# P3DA.net
KiCad netlist of a schematic drawn in EAGLE
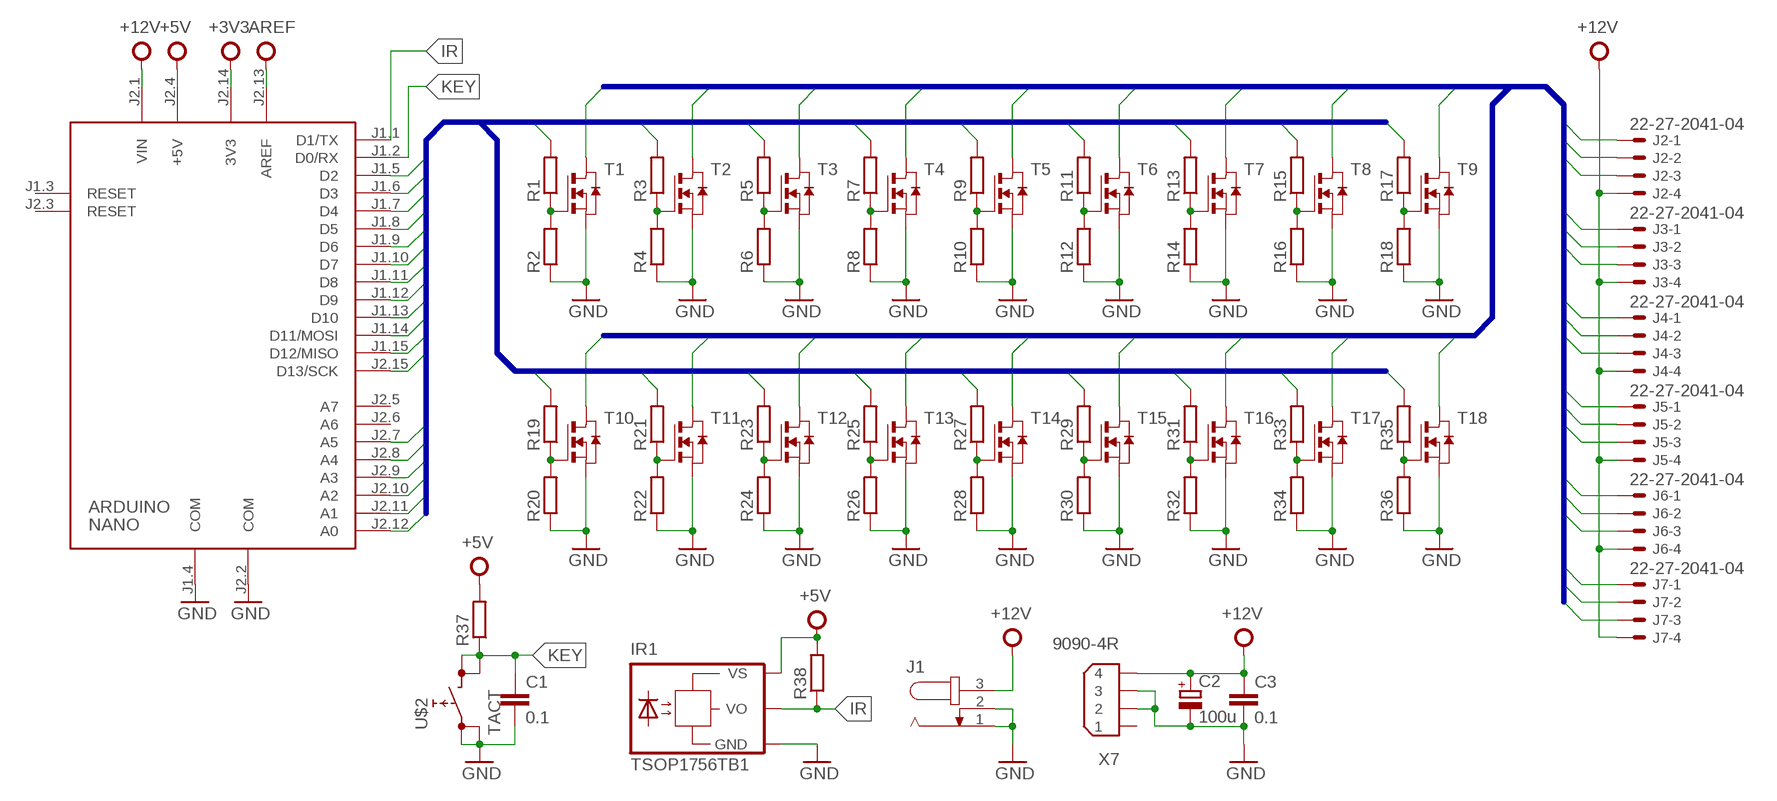
[diagram p0: schematic, sheet 1]

(export (version "E")
  (design (tool "Eeschema 10.0.6"))
  (components
    (comp (ref "ARDUINO")
      (value "NANO")
      (footprint "eagle-import:ARDUINO_NANO2")
      (libsource (lib "eagle-import") (part "ARDUINO_NANO2"))
    )
    (comp (ref "C1")
      (value "0.1")
      (footprint "eagle-import:C0805")
      (libsource (lib "eagle-import") (part "C-EUC0805"))
    )
    (comp (ref "C2")
      (value "100u")
      (footprint "eagle-import:E5-13")
      (libsource (lib "eagle-import") (part "CPOL-EUE5-13"))
    )
    (comp (ref "C3")
      (value "0.1")
      (footprint "eagle-import:C1206")
      (libsource (lib "eagle-import") (part "C-EUC1206"))
    )
    (comp (ref "IR1")
      (value "TSOP1756TB1")
      (footprint "eagle-import:TSOP17_TB1")
      (libsource (lib "eagle-import") (part "TSOP17TB156"))
    )
    (comp (ref "J1")
      (value "JACK-PLUG1")
      (footprint "eagle-import:SPC4078")
      (libsource (lib "eagle-import") (part "JACK-PLUG1"))
    )
    (comp (ref "J2")
      (value "22-27-2041-04")
      (footprint "eagle-import:6410-04")
      (libsource (lib "eagle-import") (part "22-?-0427-2041"))
    )
    (comp (ref "J3")
      (value "22-27-2041-04")
      (footprint "eagle-import:6410-04")
      (libsource (lib "eagle-import") (part "22-?-0427-2041"))
    )
    (comp (ref "J4")
      (value "22-27-2041-04")
      (footprint "eagle-import:6410-04")
      (libsource (lib "eagle-import") (part "22-?-0427-2041"))
    )
    (comp (ref "J5")
      (value "22-27-2041-04")
      (footprint "eagle-import:6410-04")
      (libsource (lib "eagle-import") (part "22-?-0427-2041"))
    )
    (comp (ref "J6")
      (value "22-27-2041-04")
      (footprint "eagle-import:6410-04")
      (libsource (lib "eagle-import") (part "22-?-0427-2041"))
    )
    (comp (ref "J7")
      (value "22-27-2041-04")
      (footprint "eagle-import:6410-04")
      (libsource (lib "eagle-import") (part "22-?-0427-2041"))
    )
    (comp (ref "R1")
      (value "R-EU_R0805")
      (footprint "eagle-import:R0805")
      (libsource (lib "eagle-import") (part "R-EU_R0805"))
    )
    (comp (ref "R2")
      (value "R-EU_R0805")
      (footprint "eagle-import:R0805")
      (libsource (lib "eagle-import") (part "R-EU_R0805"))
    )
    (comp (ref "R3")
      (value "R-EU_R0805")
      (footprint "eagle-import:R0805")
      (libsource (lib "eagle-import") (part "R-EU_R0805"))
    )
    (comp (ref "R4")
      (value "R-EU_R0805")
      (footprint "eagle-import:R0805")
      (libsource (lib "eagle-import") (part "R-EU_R0805"))
    )
    (comp (ref "R5")
      (value "R-EU_R0805")
      (footprint "eagle-import:R0805")
      (libsource (lib "eagle-import") (part "R-EU_R0805"))
    )
    (comp (ref "R6")
      (value "R-EU_R0805")
      (footprint "eagle-import:R0805")
      (libsource (lib "eagle-import") (part "R-EU_R0805"))
    )
    (comp (ref "R7")
      (value "R-EU_R0805")
      (footprint "eagle-import:R0805")
      (libsource (lib "eagle-import") (part "R-EU_R0805"))
    )
    (comp (ref "R8")
      (value "R-EU_R0805")
      (footprint "eagle-import:R0805")
      (libsource (lib "eagle-import") (part "R-EU_R0805"))
    )
    (comp (ref "R9")
      (value "R-EU_R0805")
      (footprint "eagle-import:R0805")
      (libsource (lib "eagle-import") (part "R-EU_R0805"))
    )
    (comp (ref "R10")
      (value "R-EU_R0805")
      (footprint "eagle-import:R0805")
      (libsource (lib "eagle-import") (part "R-EU_R0805"))
    )
    (comp (ref "R11")
      (value "R-EU_R0805")
      (footprint "eagle-import:R0805")
      (libsource (lib "eagle-import") (part "R-EU_R0805"))
    )
    (comp (ref "R12")
      (value "R-EU_R0805")
      (footprint "eagle-import:R0805")
      (libsource (lib "eagle-import") (part "R-EU_R0805"))
    )
    (comp (ref "R13")
      (value "R-EU_R0805")
      (footprint "eagle-import:R0805")
      (libsource (lib "eagle-import") (part "R-EU_R0805"))
    )
    (comp (ref "R14")
      (value "R-EU_R0805")
      (footprint "eagle-import:R0805")
      (libsource (lib "eagle-import") (part "R-EU_R0805"))
    )
    (comp (ref "R15")
      (value "R-EU_R0805")
      (footprint "eagle-import:R0805")
      (libsource (lib "eagle-import") (part "R-EU_R0805"))
    )
    (comp (ref "R16")
      (value "R-EU_R0805")
      (footprint "eagle-import:R0805")
      (libsource (lib "eagle-import") (part "R-EU_R0805"))
    )
    (comp (ref "R17")
      (value "R-EU_R0805")
      (footprint "eagle-import:R0805")
      (libsource (lib "eagle-import") (part "R-EU_R0805"))
    )
    (comp (ref "R18")
      (value "R-EU_R0805")
      (footprint "eagle-import:R0805")
      (libsource (lib "eagle-import") (part "R-EU_R0805"))
    )
    (comp (ref "R19")
      (value "R-EU_R0805")
      (footprint "eagle-import:R0805")
      (libsource (lib "eagle-import") (part "R-EU_R0805"))
    )
    (comp (ref "R20")
      (value "R-EU_R0805")
      (footprint "eagle-import:R0805")
      (libsource (lib "eagle-import") (part "R-EU_R0805"))
    )
    (comp (ref "R21")
      (value "R-EU_R0805")
      (footprint "eagle-import:R0805")
      (libsource (lib "eagle-import") (part "R-EU_R0805"))
    )
    (comp (ref "R22")
      (value "R-EU_R0805")
      (footprint "eagle-import:R0805")
      (libsource (lib "eagle-import") (part "R-EU_R0805"))
    )
    (comp (ref "R23")
      (value "R-EU_R0805")
      (footprint "eagle-import:R0805")
      (libsource (lib "eagle-import") (part "R-EU_R0805"))
    )
    (comp (ref "R24")
      (value "R-EU_R0805")
      (footprint "eagle-import:R0805")
      (libsource (lib "eagle-import") (part "R-EU_R0805"))
    )
    (comp (ref "R25")
      (value "R-EU_R0805")
      (footprint "eagle-import:R0805")
      (libsource (lib "eagle-import") (part "R-EU_R0805"))
    )
    (comp (ref "R26")
      (value "R-EU_R0805")
      (footprint "eagle-import:R0805")
      (libsource (lib "eagle-import") (part "R-EU_R0805"))
    )
    (comp (ref "R27")
      (value "R-EU_R0805")
      (footprint "eagle-import:R0805")
      (libsource (lib "eagle-import") (part "R-EU_R0805"))
    )
    (comp (ref "R28")
      (value "R-EU_R0805")
      (footprint "eagle-import:R0805")
      (libsource (lib "eagle-import") (part "R-EU_R0805"))
    )
    (comp (ref "R29")
      (value "R-EU_R0805")
      (footprint "eagle-import:R0805")
      (libsource (lib "eagle-import") (part "R-EU_R0805"))
    )
    (comp (ref "R30")
      (value "R-EU_R0805")
      (footprint "eagle-import:R0805")
      (libsource (lib "eagle-import") (part "R-EU_R0805"))
    )
    (comp (ref "R31")
      (value "R-EU_R0805")
      (footprint "eagle-import:R0805")
      (libsource (lib "eagle-import") (part "R-EU_R0805"))
    )
    (comp (ref "R32")
      (value "R-EU_R0805")
      (footprint "eagle-import:R0805")
      (libsource (lib "eagle-import") (part "R-EU_R0805"))
    )
    (comp (ref "R33")
      (value "R-EU_R0805")
      (footprint "eagle-import:R0805")
      (libsource (lib "eagle-import") (part "R-EU_R0805"))
    )
    (comp (ref "R34")
      (value "R-EU_R0805")
      (footprint "eagle-import:R0805")
      (libsource (lib "eagle-import") (part "R-EU_R0805"))
    )
    (comp (ref "R35")
      (value "R-EU_R0805")
      (footprint "eagle-import:R0805")
      (libsource (lib "eagle-import") (part "R-EU_R0805"))
    )
    (comp (ref "R36")
      (value "R-EU_R0805")
      (footprint "eagle-import:R0805")
      (libsource (lib "eagle-import") (part "R-EU_R0805"))
    )
    (comp (ref "R37")
      (value "R-EU_R0805")
      (footprint "eagle-import:R0805")
      (libsource (lib "eagle-import") (part "R-EU_R0805"))
    )
    (comp (ref "R38")
      (value "R-EU_R0805")
      (footprint "eagle-import:R0805")
      (libsource (lib "eagle-import") (part "R-EU_R0805"))
    )
    (comp (ref "T1")
      (value "NMOSSOT23")
      (footprint "eagle-import:SOT-23")
      (libsource (lib "eagle-import") (part "NMOSSOT23"))
    )
    (comp (ref "T2")
      (value "NMOSSOT23")
      (footprint "eagle-import:SOT-23")
      (libsource (lib "eagle-import") (part "NMOSSOT23"))
    )
    (comp (ref "T3")
      (value "NMOSSOT23")
      (footprint "eagle-import:SOT-23")
      (libsource (lib "eagle-import") (part "NMOSSOT23"))
    )
    (comp (ref "T4")
      (value "NMOSSOT23")
      (footprint "eagle-import:SOT-23")
      (libsource (lib "eagle-import") (part "NMOSSOT23"))
    )
    (comp (ref "T5")
      (value "NMOSSOT23")
      (footprint "eagle-import:SOT-23")
      (libsource (lib "eagle-import") (part "NMOSSOT23"))
    )
    (comp (ref "T6")
      (value "NMOSSOT23")
      (footprint "eagle-import:SOT-23")
      (libsource (lib "eagle-import") (part "NMOSSOT23"))
    )
    (comp (ref "T7")
      (value "NMOSSOT23")
      (footprint "eagle-import:SOT-23")
      (libsource (lib "eagle-import") (part "NMOSSOT23"))
    )
    (comp (ref "T8")
      (value "NMOSSOT23")
      (footprint "eagle-import:SOT-23")
      (libsource (lib "eagle-import") (part "NMOSSOT23"))
    )
    (comp (ref "T9")
      (value "NMOSSOT23")
      (footprint "eagle-import:SOT-23")
      (libsource (lib "eagle-import") (part "NMOSSOT23"))
    )
    (comp (ref "T10")
      (value "NMOSSOT23")
      (footprint "eagle-import:SOT-23")
      (libsource (lib "eagle-import") (part "NMOSSOT23"))
    )
    (comp (ref "T11")
      (value "NMOSSOT23")
      (footprint "eagle-import:SOT-23")
      (libsource (lib "eagle-import") (part "NMOSSOT23"))
    )
    (comp (ref "T12")
      (value "NMOSSOT23")
      (footprint "eagle-import:SOT-23")
      (libsource (lib "eagle-import") (part "NMOSSOT23"))
    )
    (comp (ref "T13")
      (value "NMOSSOT23")
      (footprint "eagle-import:SOT-23")
      (libsource (lib "eagle-import") (part "NMOSSOT23"))
    )
    (comp (ref "T14")
      (value "NMOSSOT23")
      (footprint "eagle-import:SOT-23")
      (libsource (lib "eagle-import") (part "NMOSSOT23"))
    )
    (comp (ref "T15")
      (value "NMOSSOT23")
      (footprint "eagle-import:SOT-23")
      (libsource (lib "eagle-import") (part "NMOSSOT23"))
    )
    (comp (ref "T16")
      (value "NMOSSOT23")
      (footprint "eagle-import:SOT-23")
      (libsource (lib "eagle-import") (part "NMOSSOT23"))
    )
    (comp (ref "T17")
      (value "NMOSSOT23")
      (footprint "eagle-import:SOT-23")
      (libsource (lib "eagle-import") (part "NMOSSOT23"))
    )
    (comp (ref "T18")
      (value "NMOSSOT23")
      (footprint "eagle-import:SOT-23")
      (libsource (lib "eagle-import") (part "NMOSSOT23"))
    )
    (comp (ref "U$2")
      (value "TACT")
      (footprint "eagle-import:TL1105")
      (libsource (lib "eagle-import") (part "TACT"))
    )
    (comp (ref "X7")
      (value "9090-4R")
      (footprint "eagle-import:9090-4R")
      (libsource (lib "eagle-import") (part "9090-4R"))
    )
  )
  (nets
    (net (code "1") (name "+3V3") (class "Default")
      (node (ref "ARDUINO") (pin "J2.14") (pinfunction "3V3_J2.14") (pintype "power_in"))
    )
    (net (code "2") (name "+5V") (class "Default")
      (node (ref "ARDUINO") (pin "J2.4") (pinfunction "+5V_J2.4") (pintype "power_in"))
      (node (ref "IR1") (pin "VS") (pinfunction "VS_VS") (pintype "power_in"))
      (node (ref "R37") (pin "2") (pinfunction "2_2") (pintype "passive"))
      (node (ref "R38") (pin "2") (pinfunction "2_2") (pintype "passive"))
    )
    (net (code "3") (name "+12V") (class "Default")
      (node (ref "ARDUINO") (pin "J2.1") (pinfunction "VIN_J2.1") (pintype "power_in"))
      (node (ref "C2") (pin "+") (pinfunction "+_+") (pintype "passive"))
      (node (ref "C3") (pin "1") (pinfunction "1_1") (pintype "passive"))
      (node (ref "J1") (pin "3") (pinfunction "3_3") (pintype "passive"))
      (node (ref "J2") (pin "4") (pinfunction "S_4") (pintype "passive"))
      (node (ref "J3") (pin "4") (pinfunction "S_4") (pintype "passive"))
      (node (ref "J4") (pin "4") (pinfunction "S_4") (pintype "passive"))
      (node (ref "J5") (pin "4") (pinfunction "S_4") (pintype "passive"))
      (node (ref "J6") (pin "4") (pinfunction "S_4") (pintype "passive"))
      (node (ref "J7") (pin "4") (pinfunction "S_4") (pintype "passive"))
      (node (ref "X7") (pin "4") (pinfunction "4_4") (pintype "passive"))
    )
    (net (code "4") (name "/B1") (class "Default")
      (node (ref "J2") (pin "1") (pinfunction "S_1") (pintype "passive"))
      (node (ref "T3") (pin "1") (pinfunction "D_1") (pintype "passive"))
    )
    (net (code "5") (name "/B2") (class "Default")
      (node (ref "J3") (pin "1") (pinfunction "S_1") (pintype "passive"))
      (node (ref "T6") (pin "1") (pinfunction "D_1") (pintype "passive"))
    )
    (net (code "6") (name "/B3") (class "Default")
      (node (ref "J4") (pin "1") (pinfunction "S_1") (pintype "passive"))
      (node (ref "T9") (pin "1") (pinfunction "D_1") (pintype "passive"))
    )
    (net (code "7") (name "/B4") (class "Default")
      (node (ref "J5") (pin "1") (pinfunction "S_1") (pintype "passive"))
      (node (ref "T12") (pin "1") (pinfunction "D_1") (pintype "passive"))
    )
    (net (code "8") (name "/B5") (class "Default")
      (node (ref "J6") (pin "1") (pinfunction "S_1") (pintype "passive"))
      (node (ref "T15") (pin "1") (pinfunction "D_1") (pintype "passive"))
    )
    (net (code "9") (name "/B6") (class "Default")
      (node (ref "J7") (pin "1") (pinfunction "S_1") (pintype "passive"))
      (node (ref "T18") (pin "1") (pinfunction "D_1") (pintype "passive"))
    )
    (net (code "10") (name "/B_IN1") (class "Default")
      (node (ref "ARDUINO") (pin "J1.5") (pinfunction "D2_J1.5") (pintype "bidirectional"))
      (node (ref "R5") (pin "2") (pinfunction "2_2") (pintype "passive"))
    )
    (net (code "11") (name "/B_IN2") (class "Default")
      (node (ref "ARDUINO") (pin "J1.8") (pinfunction "D5_J1.8") (pintype "bidirectional"))
      (node (ref "R11") (pin "2") (pinfunction "2_2") (pintype "passive"))
    )
    (net (code "12") (name "/B_IN3") (class "Default")
      (node (ref "ARDUINO") (pin "J1.11") (pinfunction "D8_J1.11") (pintype "bidirectional"))
      (node (ref "R17") (pin "2") (pinfunction "2_2") (pintype "passive"))
    )
    (net (code "13") (name "/B_IN4") (class "Default")
      (node (ref "ARDUINO") (pin "J2.9") (pinfunction "A3_J2.9") (pintype "bidirectional"))
      (node (ref "R23") (pin "2") (pinfunction "2_2") (pintype "passive"))
    )
    (net (code "14") (name "/B_IN5") (class "Default")
      (node (ref "ARDUINO") (pin "J2.12") (pinfunction "A0_J2.12") (pintype "bidirectional"))
      (node (ref "R29") (pin "2") (pinfunction "2_2") (pintype "passive"))
    )
    (net (code "15") (name "/B_IN6") (class "Default")
      (node (ref "ARDUINO") (pin "J1.15") (pinfunction "D12/MISO_J1.15") (pintype "bidirectional"))
      (node (ref "R35") (pin "2") (pinfunction "2_2") (pintype "passive"))
    )
    (net (code "16") (name "/G1") (class "Default")
      (node (ref "J2") (pin "3") (pinfunction "S_3") (pintype "passive"))
      (node (ref "T2") (pin "1") (pinfunction "D_1") (pintype "passive"))
    )
    (net (code "17") (name "/G2") (class "Default")
      (node (ref "J3") (pin "3") (pinfunction "S_3") (pintype "passive"))
      (node (ref "T5") (pin "1") (pinfunction "D_1") (pintype "passive"))
    )
    (net (code "18") (name "/G3") (class "Default")
      (node (ref "J4") (pin "3") (pinfunction "S_3") (pintype "passive"))
      (node (ref "T8") (pin "1") (pinfunction "D_1") (pintype "passive"))
    )
    (net (code "19") (name "/G4") (class "Default")
      (node (ref "J5") (pin "3") (pinfunction "S_3") (pintype "passive"))
      (node (ref "T11") (pin "1") (pinfunction "D_1") (pintype "passive"))
    )
    (net (code "20") (name "/G5") (class "Default")
      (node (ref "J6") (pin "3") (pinfunction "S_3") (pintype "passive"))
      (node (ref "T14") (pin "1") (pinfunction "D_1") (pintype "passive"))
    )
    (net (code "21") (name "/G6") (class "Default")
      (node (ref "J7") (pin "3") (pinfunction "S_3") (pintype "passive"))
      (node (ref "T17") (pin "1") (pinfunction "D_1") (pintype "passive"))
    )
    (net (code "22") (name "/G_IN1") (class "Default")
      (node (ref "ARDUINO") (pin "J1.7") (pinfunction "D4_J1.7") (pintype "bidirectional"))
      (node (ref "R3") (pin "2") (pinfunction "2_2") (pintype "passive"))
    )
    (net (code "23") (name "/G_IN2") (class "Default")
      (node (ref "ARDUINO") (pin "J1.10") (pinfunction "D7_J1.10") (pintype "bidirectional"))
      (node (ref "R9") (pin "2") (pinfunction "2_2") (pintype "passive"))
    )
    (net (code "24") (name "/G_IN3") (class "Default")
      (node (ref "ARDUINO") (pin "J1.13") (pinfunction "D10_J1.13") (pintype "bidirectional"))
      (node (ref "R15") (pin "2") (pinfunction "2_2") (pintype "passive"))
    )
    (net (code "25") (name "/G_IN4") (class "Default")
      (node (ref "ARDUINO") (pin "J2.7") (pinfunction "A5_J2.7") (pintype "bidirectional"))
      (node (ref "R21") (pin "2") (pinfunction "2_2") (pintype "passive"))
    )
    (net (code "26") (name "/G_IN5") (class "Default")
      (node (ref "ARDUINO") (pin "J2.10") (pinfunction "A2_J2.10") (pintype "bidirectional"))
      (node (ref "R27") (pin "2") (pinfunction "2_2") (pintype "passive"))
    )
    (net (code "27") (name "/G_IN6") (class "Default")
      (node (ref "ARDUINO") (pin "J2.15") (pinfunction "D13/SCK_J2.15") (pintype "bidirectional"))
      (node (ref "R33") (pin "2") (pinfunction "2_2") (pintype "passive"))
    )
    (net (code "28") (name "/R1") (class "Default")
      (node (ref "J2") (pin "2") (pinfunction "S_2") (pintype "passive"))
      (node (ref "T1") (pin "1") (pinfunction "D_1") (pintype "passive"))
    )
    (net (code "29") (name "/R2") (class "Default")
      (node (ref "J3") (pin "2") (pinfunction "S_2") (pintype "passive"))
      (node (ref "T4") (pin "1") (pinfunction "D_1") (pintype "passive"))
    )
    (net (code "30") (name "/R3") (class "Default")
      (node (ref "J4") (pin "2") (pinfunction "S_2") (pintype "passive"))
      (node (ref "T7") (pin "1") (pinfunction "D_1") (pintype "passive"))
    )
    (net (code "31") (name "/R4") (class "Default")
      (node (ref "J5") (pin "2") (pinfunction "S_2") (pintype "passive"))
      (node (ref "T10") (pin "1") (pinfunction "D_1") (pintype "passive"))
    )
    (net (code "32") (name "/R5") (class "Default")
      (node (ref "J6") (pin "2") (pinfunction "S_2") (pintype "passive"))
      (node (ref "T13") (pin "1") (pinfunction "D_1") (pintype "passive"))
    )
    (net (code "33") (name "/R6") (class "Default")
      (node (ref "J7") (pin "2") (pinfunction "S_2") (pintype "passive"))
      (node (ref "T16") (pin "1") (pinfunction "D_1") (pintype "passive"))
    )
    (net (code "34") (name "/R_IN1") (class "Default")
      (node (ref "ARDUINO") (pin "J1.6") (pinfunction "D3_J1.6") (pintype "bidirectional"))
      (node (ref "R1") (pin "2") (pinfunction "2_2") (pintype "passive"))
    )
    (net (code "35") (name "/R_IN2") (class "Default")
      (node (ref "ARDUINO") (pin "J1.9") (pinfunction "D6_J1.9") (pintype "bidirectional"))
      (node (ref "R7") (pin "2") (pinfunction "2_2") (pintype "passive"))
    )
    (net (code "36") (name "/R_IN3") (class "Default")
      (node (ref "ARDUINO") (pin "J1.12") (pinfunction "D9_J1.12") (pintype "bidirectional"))
      (node (ref "R13") (pin "2") (pinfunction "2_2") (pintype "passive"))
    )
    (net (code "37") (name "/R_IN4") (class "Default")
      (node (ref "ARDUINO") (pin "J2.8") (pinfunction "A4_J2.8") (pintype "bidirectional"))
      (node (ref "R19") (pin "2") (pinfunction "2_2") (pintype "passive"))
    )
    (net (code "38") (name "/R_IN5") (class "Default")
      (node (ref "ARDUINO") (pin "J2.11") (pinfunction "A1_J2.11") (pintype "bidirectional"))
      (node (ref "R25") (pin "2") (pinfunction "2_2") (pintype "passive"))
    )
    (net (code "39") (name "/R_IN6") (class "Default")
      (node (ref "ARDUINO") (pin "J1.14") (pinfunction "D11/MOSI_J1.14") (pintype "bidirectional"))
      (node (ref "R31") (pin "2") (pinfunction "2_2") (pintype "passive"))
    )
    (net (code "40") (name "AREF") (class "Default")
      (node (ref "ARDUINO") (pin "J2.13") (pinfunction "AREF_J2.13") (pintype "power_in"))
    )
    (net (code "41") (name "GND") (class "Default")
      (node (ref "ARDUINO") (pin "J1.4") (pinfunction "COM_J1.4") (pintype "power_in"))
      (node (ref "ARDUINO") (pin "J2.2") (pinfunction "COM_J2.2") (pintype "power_in"))
      (node (ref "C1") (pin "2") (pinfunction "2_2") (pintype "passive"))
      (node (ref "C2") (pin "-") (pinfunction "-_-") (pintype "passive"))
      (node (ref "C3") (pin "2") (pinfunction "2_2") (pintype "passive"))
      (node (ref "IR1") (pin "GND") (pinfunction "GND_GND") (pintype "power_in"))
      (node (ref "J1") (pin "1") (pinfunction "1_1") (pintype "passive"))
      (node (ref "J1") (pin "2") (pinfunction "2_2") (pintype "passive"))
      (node (ref "R10") (pin "1") (pinfunction "1_1") (pintype "passive"))
      (node (ref "R12") (pin "1") (pinfunction "1_1") (pintype "passive"))
      (node (ref "R14") (pin "1") (pinfunction "1_1") (pintype "passive"))
      (node (ref "R16") (pin "1") (pinfunction "1_1") (pintype "passive"))
      (node (ref "R18") (pin "1") (pinfunction "1_1") (pintype "passive"))
      (node (ref "R2") (pin "1") (pinfunction "1_1") (pintype "passive"))
      (node (ref "R20") (pin "1") (pinfunction "1_1") (pintype "passive"))
      (node (ref "R22") (pin "1") (pinfunction "1_1") (pintype "passive"))
      (node (ref "R24") (pin "1") (pinfunction "1_1") (pintype "passive"))
      (node (ref "R26") (pin "1") (pinfunction "1_1") (pintype "passive"))
      (node (ref "R28") (pin "1") (pinfunction "1_1") (pintype "passive"))
      (node (ref "R30") (pin "1") (pinfunction "1_1") (pintype "passive"))
      (node (ref "R32") (pin "1") (pinfunction "1_1") (pintype "passive"))
      (node (ref "R34") (pin "1") (pinfunction "1_1") (pintype "passive"))
      (node (ref "R36") (pin "1") (pinfunction "1_1") (pintype "passive"))
      (node (ref "R4") (pin "1") (pinfunction "1_1") (pintype "passive"))
      (node (ref "R6") (pin "1") (pinfunction "1_1") (pintype "passive"))
      (node (ref "R8") (pin "1") (pinfunction "1_1") (pintype "passive"))
      (node (ref "T1") (pin "2") (pinfunction "S_2") (pintype "passive"))
      (node (ref "T10") (pin "2") (pinfunction "S_2") (pintype "passive"))
      (node (ref "T11") (pin "2") (pinfunction "S_2") (pintype "passive"))
      (node (ref "T12") (pin "2") (pinfunction "S_2") (pintype "passive"))
      (node (ref "T13") (pin "2") (pinfunction "S_2") (pintype "passive"))
      (node (ref "T14") (pin "2") (pinfunction "S_2") (pintype "passive"))
      (node (ref "T15") (pin "2") (pinfunction "S_2") (pintype "passive"))
      (node (ref "T16") (pin "2") (pinfunction "S_2") (pintype "passive"))
      (node (ref "T17") (pin "2") (pinfunction "S_2") (pintype "passive"))
      (node (ref "T18") (pin "2") (pinfunction "S_2") (pintype "passive"))
      (node (ref "T2") (pin "2") (pinfunction "S_2") (pintype "passive"))
      (node (ref "T3") (pin "2") (pinfunction "S_2") (pintype "passive"))
      (node (ref "T4") (pin "2") (pinfunction "S_2") (pintype "passive"))
      (node (ref "T5") (pin "2") (pinfunction "S_2") (pintype "passive"))
      (node (ref "T6") (pin "2") (pinfunction "S_2") (pintype "passive"))
      (node (ref "T7") (pin "2") (pinfunction "S_2") (pintype "passive"))
      (node (ref "T8") (pin "2") (pinfunction "S_2") (pintype "passive"))
      (node (ref "T9") (pin "2") (pinfunction "S_2") (pintype "passive"))
      (node (ref "U$2") (pin "1") (pinfunction "0_1") (pintype "passive"))
      (node (ref "U$2") (pin "3") (pinfunction "0_3") (pintype "passive"))
      (node (ref "X7") (pin "2") (pinfunction "2_2") (pintype "passive"))
      (node (ref "X7") (pin "3") (pinfunction "3_3") (pintype "passive"))
    )
    (net (code "42") (name "IR") (class "Default")
      (node (ref "ARDUINO") (pin "J1.1") (pinfunction "D1/TX_J1.1") (pintype "bidirectional"))
      (node (ref "IR1") (pin "VO") (pinfunction "VO_VO") (pintype "open_collector"))
      (node (ref "R38") (pin "1") (pinfunction "1_1") (pintype "passive"))
    )
    (net (code "43") (name "KEY") (class "Default")
      (node (ref "ARDUINO") (pin "J1.2") (pinfunction "D0/RX_J1.2") (pintype "bidirectional"))
      (node (ref "C1") (pin "1") (pinfunction "1_1") (pintype "passive"))
      (node (ref "R37") (pin "1") (pinfunction "1_1") (pintype "passive"))
      (node (ref "U$2") (pin "2") (pinfunction "1_2") (pintype "passive"))
      (node (ref "U$2") (pin "4") (pinfunction "1_4") (pintype "passive"))
    )
    (net (code "44") (name "Net-(T1-G)") (class "Default")
      (node (ref "R1") (pin "1") (pinfunction "1_1") (pintype "passive"))
      (node (ref "R2") (pin "2") (pinfunction "2_2") (pintype "passive"))
      (node (ref "T1") (pin "3") (pinfunction "G_3") (pintype "passive"))
    )
    (net (code "45") (name "Net-(T2-G)") (class "Default")
      (node (ref "R3") (pin "1") (pinfunction "1_1") (pintype "passive"))
      (node (ref "R4") (pin "2") (pinfunction "2_2") (pintype "passive"))
      (node (ref "T2") (pin "3") (pinfunction "G_3") (pintype "passive"))
    )
    (net (code "46") (name "Net-(T3-G)") (class "Default")
      (node (ref "R5") (pin "1") (pinfunction "1_1") (pintype "passive"))
      (node (ref "R6") (pin "2") (pinfunction "2_2") (pintype "passive"))
      (node (ref "T3") (pin "3") (pinfunction "G_3") (pintype "passive"))
    )
    (net (code "47") (name "Net-(T4-G)") (class "Default")
      (node (ref "R7") (pin "1") (pinfunction "1_1") (pintype "passive"))
      (node (ref "R8") (pin "2") (pinfunction "2_2") (pintype "passive"))
      (node (ref "T4") (pin "3") (pinfunction "G_3") (pintype "passive"))
    )
    (net (code "48") (name "Net-(T5-G)") (class "Default")
      (node (ref "R10") (pin "2") (pinfunction "2_2") (pintype "passive"))
      (node (ref "R9") (pin "1") (pinfunction "1_1") (pintype "passive"))
      (node (ref "T5") (pin "3") (pinfunction "G_3") (pintype "passive"))
    )
    (net (code "49") (name "Net-(T6-G)") (class "Default")
      (node (ref "R11") (pin "1") (pinfunction "1_1") (pintype "passive"))
      (node (ref "R12") (pin "2") (pinfunction "2_2") (pintype "passive"))
      (node (ref "T6") (pin "3") (pinfunction "G_3") (pintype "passive"))
    )
    (net (code "50") (name "Net-(T7-G)") (class "Default")
      (node (ref "R13") (pin "1") (pinfunction "1_1") (pintype "passive"))
      (node (ref "R14") (pin "2") (pinfunction "2_2") (pintype "passive"))
      (node (ref "T7") (pin "3") (pinfunction "G_3") (pintype "passive"))
    )
    (net (code "51") (name "Net-(T8-G)") (class "Default")
      (node (ref "R15") (pin "1") (pinfunction "1_1") (pintype "passive"))
      (node (ref "R16") (pin "2") (pinfunction "2_2") (pintype "passive"))
      (node (ref "T8") (pin "3") (pinfunction "G_3") (pintype "passive"))
    )
    (net (code "52") (name "Net-(T9-G)") (class "Default")
      (node (ref "R17") (pin "1") (pinfunction "1_1") (pintype "passive"))
      (node (ref "R18") (pin "2") (pinfunction "2_2") (pintype "passive"))
      (node (ref "T9") (pin "3") (pinfunction "G_3") (pintype "passive"))
    )
    (net (code "53") (name "Net-(T10-G)") (class "Default")
      (node (ref "R19") (pin "1") (pinfunction "1_1") (pintype "passive"))
      (node (ref "R20") (pin "2") (pinfunction "2_2") (pintype "passive"))
      (node (ref "T10") (pin "3") (pinfunction "G_3") (pintype "passive"))
    )
    (net (code "54") (name "Net-(T11-G)") (class "Default")
      (node (ref "R21") (pin "1") (pinfunction "1_1") (pintype "passive"))
      (node (ref "R22") (pin "2") (pinfunction "2_2") (pintype "passive"))
      (node (ref "T11") (pin "3") (pinfunction "G_3") (pintype "passive"))
    )
    (net (code "55") (name "Net-(T12-G)") (class "Default")
      (node (ref "R23") (pin "1") (pinfunction "1_1") (pintype "passive"))
      (node (ref "R24") (pin "2") (pinfunction "2_2") (pintype "passive"))
      (node (ref "T12") (pin "3") (pinfunction "G_3") (pintype "passive"))
    )
    (net (code "56") (name "Net-(T13-G)") (class "Default")
      (node (ref "R25") (pin "1") (pinfunction "1_1") (pintype "passive"))
      (node (ref "R26") (pin "2") (pinfunction "2_2") (pintype "passive"))
      (node (ref "T13") (pin "3") (pinfunction "G_3") (pintype "passive"))
    )
    (net (code "57") (name "Net-(T14-G)") (class "Default")
      (node (ref "R27") (pin "1") (pinfunction "1_1") (pintype "passive"))
      (node (ref "R28") (pin "2") (pinfunction "2_2") (pintype "passive"))
      (node (ref "T14") (pin "3") (pinfunction "G_3") (pintype "passive"))
    )
    (net (code "58") (name "Net-(T15-G)") (class "Default")
      (node (ref "R29") (pin "1") (pinfunction "1_1") (pintype "passive"))
      (node (ref "R30") (pin "2") (pinfunction "2_2") (pintype "passive"))
      (node (ref "T15") (pin "3") (pinfunction "G_3") (pintype "passive"))
    )
    (net (code "59") (name "Net-(T16-G)") (class "Default")
      (node (ref "R31") (pin "1") (pinfunction "1_1") (pintype "passive"))
      (node (ref "R32") (pin "2") (pinfunction "2_2") (pintype "passive"))
      (node (ref "T16") (pin "3") (pinfunction "G_3") (pintype "passive"))
    )
    (net (code "60") (name "Net-(T17-G)") (class "Default")
      (node (ref "R33") (pin "1") (pinfunction "1_1") (pintype "passive"))
      (node (ref "R34") (pin "2") (pinfunction "2_2") (pintype "passive"))
      (node (ref "T17") (pin "3") (pinfunction "G_3") (pintype "passive"))
    )
    (net (code "61") (name "Net-(T18-G)") (class "Default")
      (node (ref "R35") (pin "1") (pinfunction "1_1") (pintype "passive"))
      (node (ref "R36") (pin "2") (pinfunction "2_2") (pintype "passive"))
      (node (ref "T18") (pin "3") (pinfunction "G_3") (pintype "passive"))
    )
    (net (code "62") (name "unconnected-(ARDUINO-A6-PadJ2.6)") (class "Default")
      (node (ref "ARDUINO") (pin "J2.6") (pinfunction "A6_J2.6") (pintype "bidirectional"))
    )
    (net (code "63") (name "unconnected-(ARDUINO-A7-PadJ2.5)") (class "Default")
      (node (ref "ARDUINO") (pin "J2.5") (pinfunction "A7_J2.5") (pintype "bidirectional"))
    )
    (net (code "64") (name "unconnected-(ARDUINO-RESET-PadJ1.3)") (class "Default")
      (node (ref "ARDUINO") (pin "J1.3") (pinfunction "RESET_J1.3") (pintype "bidirectional"))
    )
    (net (code "65") (name "unconnected-(ARDUINO-RESET-PadJ2.3)") (class "Default")
      (node (ref "ARDUINO") (pin "J2.3") (pinfunction "RESET_J2.3") (pintype "bidirectional"))
    )
    (net (code "66") (name "unconnected-(X7-Pad1)") (class "Default")
      (node (ref "X7") (pin "1") (pinfunction "1_1") (pintype "passive"))
    )
  )
)
